# Encoder.net
KiCad netlist of a schematic drawn in Altium Designer
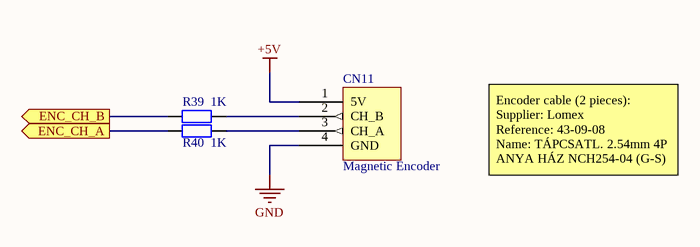
[diagram p0: Encoder.SchDoc]

(export (version "E")
  (design (tool "Eeschema 10.0.6"))
  (components
    (comp (ref "CN11")
      (value "Magnetic Encoder")
      (footprint "FP_CONN4_TAP_254MM")
      (description "Allegro A1333 Magnetic Encoder")
      (libsource (lib "LKBulls2023") (part "Connector_Encoder"))
    )
    (comp (ref "R39")
      (value "1K")
      (footprint "FP_0805_RES")
      (description "Resistor")
      (fields (field (name "TOLERANCE") "5%") (field (name "POWER") "0.125W"))
      (libsource (lib "LKBulls2023") (part "RES"))
    )
    (comp (ref "R40")
      (value "1K")
      (footprint "FP_0805_RES")
      (description "Resistor")
      (fields (field (name "TOLERANCE") "5%") (field (name "POWER") "0.125W"))
      (libsource (lib "LKBulls2023") (part "RES"))
    )
  )
  (nets
    (net (code "1") (name "+5V") (class "Default")
      (node (ref "CN11") (pin "1") (pinfunction "5V_1") (pintype "power_in"))
    )
    (net (code "2") (name "/ENC_CH_A") (class "Default")
      (node (ref "R40") (pin "1") (pinfunction "1_1") (pintype "passive"))
    )
    (net (code "3") (name "/ENC_CH_B") (class "Default")
      (node (ref "R39") (pin "1") (pinfunction "1_1") (pintype "passive"))
    )
    (net (code "4") (name "GND") (class "Default")
      (node (ref "CN11") (pin "4") (pinfunction "GND_4") (pintype "passive"))
    )
    (net (code "5") (name "Net-(CN11-CH_A)") (class "Default")
      (node (ref "CN11") (pin "3") (pinfunction "CH_A_3") (pintype "output"))
      (node (ref "R40") (pin "2") (pinfunction "2_2") (pintype "passive"))
    )
    (net (code "6") (name "Net-(CN11-CH_B)") (class "Default")
      (node (ref "CN11") (pin "2") (pinfunction "CH_B_2") (pintype "output"))
      (node (ref "R39") (pin "2") (pinfunction "2_2") (pintype "passive"))
    )
  )
)
